# IR.net
KiCad netlist of a schematic drawn in Altium Designer
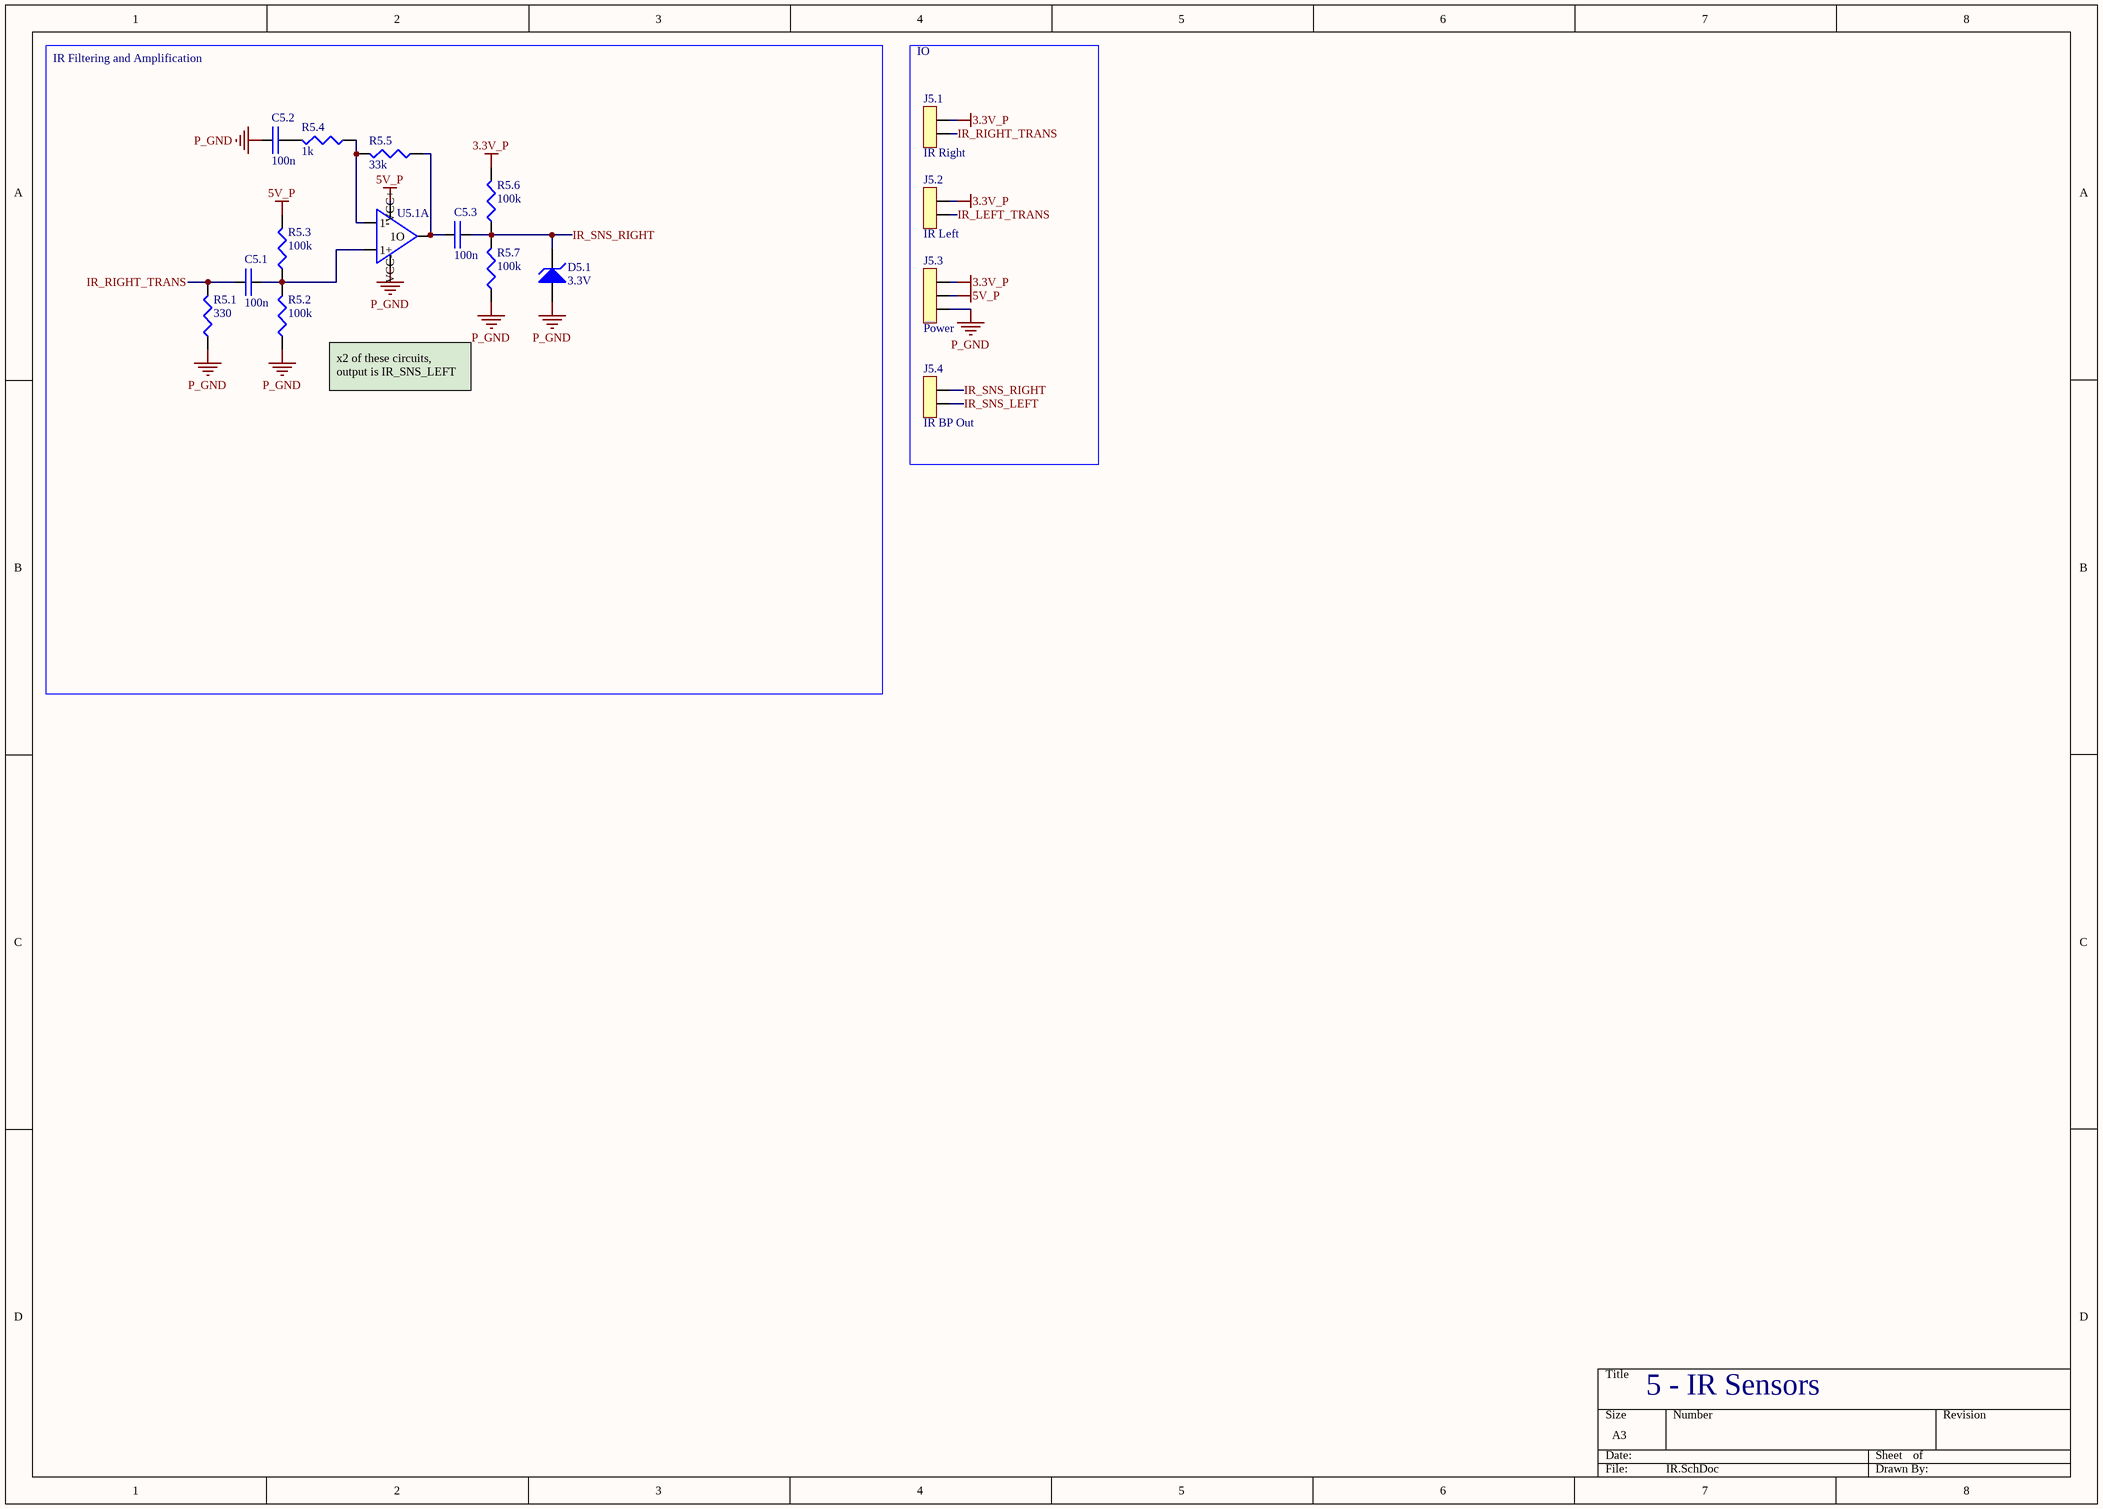
[diagram p0: IR.SchDoc]

(export (version "E")
  (design (tool "Eeschema 10.0.6"))
  (components
    (comp (ref "C5.1")
      (value "100n")
      (footprint "Non Polarized Cap")
      (libsource (lib "SPICEBot_SchLib") (part "Cap_Generic"))
    )
    (comp (ref "C5.2")
      (value "100n")
      (footprint "Non Polarized Cap")
      (libsource (lib "SPICEBot_SchLib") (part "Cap_Generic"))
    )
    (comp (ref "C5.3")
      (value "100n")
      (footprint "Non Polarized Cap")
      (libsource (lib "SPICEBot_SchLib") (part "Cap_Generic"))
    )
    (comp (ref "D5.1")
      (value "3.3V")
      (footprint "Zener Generic")
      (libsource (lib "SPICEBot_SchLib") (part "Zener_Generic"))
    )
    (comp (ref "J5.1")
      (value "IR Right")
      (footprint "2pos JST")
      (description "2pos Conn JST")
      (libsource (lib "SPICEBot_SchLib") (part "2pos Conn"))
    )
    (comp (ref "J5.2")
      (value "IR Left")
      (footprint "2pos JST")
      (description "2pos Conn JST")
      (libsource (lib "SPICEBot_SchLib") (part "2pos Conn"))
    )
    (comp (ref "J5.3")
      (value "Power")
      (footprint "3pos JST")
      (description "3pos Conn")
      (libsource (lib "SPICEBot_SchLib") (part "3pos Conn"))
    )
    (comp (ref "J5.4")
      (value "IR BP Out")
      (footprint "2pos JST")
      (description "2pos Conn JST")
      (libsource (lib "SPICEBot_SchLib") (part "2pos Conn"))
    )
    (comp (ref "R5.1")
      (value "330")
      (footprint "Res_Generic")
      (libsource (lib "SPICEBot_SchLib") (part "Res_Generic"))
    )
    (comp (ref "R5.2")
      (value "100k")
      (footprint "Res_Generic")
      (libsource (lib "SPICEBot_SchLib") (part "Res_Generic"))
    )
    (comp (ref "R5.3")
      (value "100k")
      (footprint "Res_Generic")
      (libsource (lib "SPICEBot_SchLib") (part "Res_Generic"))
    )
    (comp (ref "R5.4")
      (value "1k")
      (footprint "Res_Generic")
      (libsource (lib "SPICEBot_SchLib") (part "Res_Generic"))
    )
    (comp (ref "R5.5")
      (value "33k")
      (footprint "Res_Generic")
      (libsource (lib "SPICEBot_SchLib") (part "Res_Generic"))
    )
    (comp (ref "R5.6")
      (value "100k")
      (footprint "Res_Generic")
      (libsource (lib "SPICEBot_SchLib") (part "Res_Generic"))
    )
    (comp (ref "R5.7")
      (value "100k")
      (footprint "Res_Generic")
      (libsource (lib "SPICEBot_SchLib") (part "Res_Generic"))
    )
    (comp (ref "U5.1")
      (value "TL082IP")
      (footprint "DIP8")
      (description "TL082IP IC OPAMP JFET 2 CIRCUIT 8DIP")
      (libsource (lib "SPICEBot_SchLib") (part "TL082IP Op Amp"))
    )
  )
  (nets
    (net (code "1") (name "/IR_LEFT_TRANS") (class "Default")
      (node (ref "J5.2") (pin "1") (pinfunction "1_1") (pintype "passive"))
    )
    (net (code "2") (name "/IR_RIGHT_TRANS") (class "Default")
      (node (ref "C5.1") (pin "1") (pinfunction "1_1") (pintype "passive"))
      (node (ref "J5.1") (pin "1") (pinfunction "1_1") (pintype "passive"))
      (node (ref "R5.1") (pin "2") (pinfunction "2_2") (pintype "passive"))
    )
    (net (code "3") (name "/IR_SNS_LEFT") (class "Default")
      (node (ref "J5.4") (pin "1") (pinfunction "1_1") (pintype "passive"))
    )
    (net (code "4") (name "/IR_SNS_RIGHT") (class "Default")
      (node (ref "C5.3") (pin "2") (pinfunction "2_2") (pintype "passive"))
      (node (ref "D5.1") (pin "2") (pinfunction "Cathode_2") (pintype "passive"))
      (node (ref "J5.4") (pin "2") (pinfunction "2_2") (pintype "passive"))
      (node (ref "R5.6") (pin "1") (pinfunction "1_1") (pintype "passive"))
      (node (ref "R5.7") (pin "2") (pinfunction "2_2") (pintype "passive"))
    )
    (net (code "5") (name "3.3V_P") (class "Default")
      (node (ref "J5.1") (pin "2") (pinfunction "2_2") (pintype "passive"))
      (node (ref "J5.2") (pin "2") (pinfunction "2_2") (pintype "passive"))
      (node (ref "J5.3") (pin "3") (pinfunction "3_3") (pintype "passive"))
      (node (ref "R5.6") (pin "2") (pinfunction "2_2") (pintype "passive"))
    )
    (net (code "6") (name "5V_P") (class "Default")
      (node (ref "J5.3") (pin "2") (pinfunction "2_2") (pintype "passive"))
      (node (ref "R5.3") (pin "2") (pinfunction "2_2") (pintype "passive"))
      (node (ref "U5.1") (pin "8") (pinfunction "VCC+_8") (pintype "passive"))
    )
    (net (code "7") (name "Net-(C5.2-Pad2)") (class "Default")
      (node (ref "C5.2") (pin "2") (pinfunction "2_2") (pintype "passive"))
      (node (ref "R5.4") (pin "2") (pinfunction "2_2") (pintype "passive"))
    )
    (net (code "8") (name "Net-(U5.1A-1+)") (class "Default")
      (node (ref "C5.1") (pin "2") (pinfunction "2_2") (pintype "passive"))
      (node (ref "R5.2") (pin "2") (pinfunction "2_2") (pintype "passive"))
      (node (ref "R5.3") (pin "1") (pinfunction "1_1") (pintype "passive"))
      (node (ref "U5.1") (pin "3") (pinfunction "1+_3") (pintype "passive"))
    )
    (net (code "9") (name "Net-(U5.1A-1-)") (class "Default")
      (node (ref "R5.4") (pin "1") (pinfunction "1_1") (pintype "passive"))
      (node (ref "R5.5") (pin "2") (pinfunction "2_2") (pintype "passive"))
      (node (ref "U5.1") (pin "2") (pinfunction "1-_2") (pintype "passive"))
    )
    (net (code "10") (name "Net-(U5.1A-1O)") (class "Default")
      (node (ref "C5.3") (pin "1") (pinfunction "1_1") (pintype "passive"))
      (node (ref "R5.5") (pin "1") (pinfunction "1_1") (pintype "passive"))
      (node (ref "U5.1") (pin "1") (pinfunction "1O_1") (pintype "passive"))
    )
    (net (code "11") (name "P_GND") (class "Default")
      (node (ref "C5.2") (pin "1") (pinfunction "1_1") (pintype "passive"))
      (node (ref "D5.1") (pin "1") (pinfunction "Anode_1") (pintype "passive"))
      (node (ref "J5.3") (pin "1") (pinfunction "1_1") (pintype "passive"))
      (node (ref "R5.1") (pin "1") (pinfunction "1_1") (pintype "passive"))
      (node (ref "R5.2") (pin "1") (pinfunction "1_1") (pintype "passive"))
      (node (ref "R5.7") (pin "1") (pinfunction "1_1") (pintype "passive"))
      (node (ref "U5.1") (pin "4") (pinfunction "VCC-_4") (pintype "passive"))
    )
  )
)
